# poker_shematics_3.net
KiCad netlist of a schematic drawn in Altium Designer
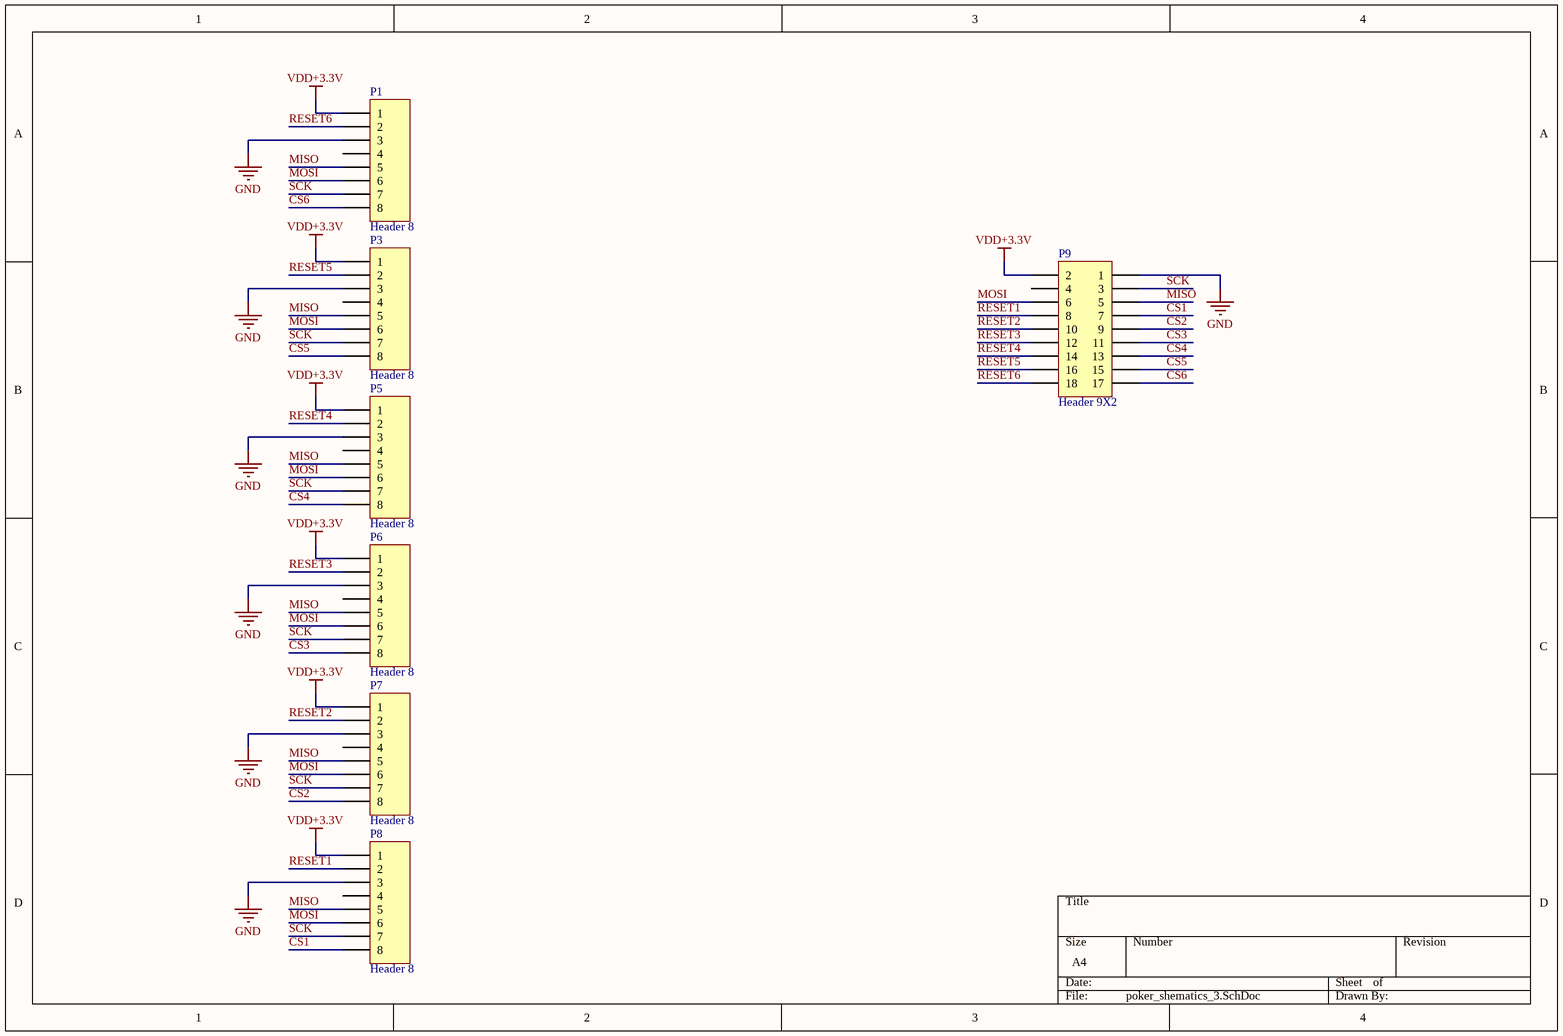
[diagram p0: poker_shematics_3.SchDoc]

(export (version "E")
  (design (tool "Eeschema 10.0.6"))
  (components
    (comp (ref "P1")
      (value "Header 8")
      (footprint "HDR1X8")
      (description "Header, 8-Pin")
      (fields (field (name "PUBLISHER") "Altium Limited"))
      (libsource (lib "Miscellaneous Connectors") (part "Header 8"))
    )
    (comp (ref "P3")
      (value "Header 8")
      (footprint "HDR1X8")
      (description "Header, 8-Pin")
      (fields (field (name "PUBLISHER") "Altium Limited"))
      (libsource (lib "Miscellaneous Connectors") (part "Header 8"))
    )
    (comp (ref "P5")
      (value "Header 8")
      (footprint "HDR1X8")
      (description "Header, 8-Pin")
      (fields (field (name "PUBLISHER") "Altium Limited"))
      (libsource (lib "Miscellaneous Connectors") (part "Header 8"))
    )
    (comp (ref "P6")
      (value "Header 8")
      (footprint "HDR1X8")
      (description "Header, 8-Pin")
      (fields (field (name "PUBLISHER") "Altium Limited"))
      (libsource (lib "Miscellaneous Connectors") (part "Header 8"))
    )
    (comp (ref "P7")
      (value "Header 8")
      (footprint "HDR1X8")
      (description "Header, 8-Pin")
      (fields (field (name "PUBLISHER") "Altium Limited"))
      (libsource (lib "Miscellaneous Connectors") (part "Header 8"))
    )
    (comp (ref "P8")
      (value "Header 8")
      (footprint "HDR1X8")
      (description "Header, 8-Pin")
      (fields (field (name "PUBLISHER") "Altium Limited"))
      (libsource (lib "Miscellaneous Connectors") (part "Header 8"))
    )
    (comp (ref "P9")
      (value "Header 9X2")
      (footprint "HDR2X9")
      (description "Header, 9-Pin, Dual row")
      (fields (field (name "PUBLISHER") "Altium Limited"))
      (libsource (lib "Miscellaneous Connectors") (part "Header 9X2"))
    )
  )
  (nets
    (net (code "1") (name "/CS1") (class "Default")
      (node (ref "P8") (pin "8") (pinfunction "8_8") (pintype "passive"))
      (node (ref "P9") (pin "7") (pinfunction "7_7") (pintype "passive"))
    )
    (net (code "2") (name "/CS2") (class "Default")
      (node (ref "P7") (pin "8") (pinfunction "8_8") (pintype "passive"))
      (node (ref "P9") (pin "9") (pinfunction "9_9") (pintype "passive"))
    )
    (net (code "3") (name "/CS3") (class "Default")
      (node (ref "P6") (pin "8") (pinfunction "8_8") (pintype "passive"))
      (node (ref "P9") (pin "11") (pinfunction "11_11") (pintype "passive"))
    )
    (net (code "4") (name "/CS4") (class "Default")
      (node (ref "P5") (pin "8") (pinfunction "8_8") (pintype "passive"))
      (node (ref "P9") (pin "13") (pinfunction "13_13") (pintype "passive"))
    )
    (net (code "5") (name "/CS5") (class "Default")
      (node (ref "P3") (pin "8") (pinfunction "8_8") (pintype "passive"))
      (node (ref "P9") (pin "15") (pinfunction "15_15") (pintype "passive"))
    )
    (net (code "6") (name "/CS6") (class "Default")
      (node (ref "P1") (pin "8") (pinfunction "8_8") (pintype "passive"))
      (node (ref "P9") (pin "17") (pinfunction "17_17") (pintype "passive"))
    )
    (net (code "7") (name "/MISO") (class "Default")
      (node (ref "P1") (pin "5") (pinfunction "5_5") (pintype "passive"))
      (node (ref "P3") (pin "5") (pinfunction "5_5") (pintype "passive"))
      (node (ref "P5") (pin "5") (pinfunction "5_5") (pintype "passive"))
      (node (ref "P6") (pin "5") (pinfunction "5_5") (pintype "passive"))
      (node (ref "P7") (pin "5") (pinfunction "5_5") (pintype "passive"))
      (node (ref "P8") (pin "5") (pinfunction "5_5") (pintype "passive"))
      (node (ref "P9") (pin "5") (pinfunction "5_5") (pintype "passive"))
    )
    (net (code "8") (name "/MOSI") (class "Default")
      (node (ref "P1") (pin "6") (pinfunction "6_6") (pintype "passive"))
      (node (ref "P3") (pin "6") (pinfunction "6_6") (pintype "passive"))
      (node (ref "P5") (pin "6") (pinfunction "6_6") (pintype "passive"))
      (node (ref "P6") (pin "6") (pinfunction "6_6") (pintype "passive"))
      (node (ref "P7") (pin "6") (pinfunction "6_6") (pintype "passive"))
      (node (ref "P8") (pin "6") (pinfunction "6_6") (pintype "passive"))
      (node (ref "P9") (pin "6") (pinfunction "6_6") (pintype "passive"))
    )
    (net (code "9") (name "/RESET1") (class "Default")
      (node (ref "P8") (pin "2") (pinfunction "2_2") (pintype "passive"))
      (node (ref "P9") (pin "8") (pinfunction "8_8") (pintype "passive"))
    )
    (net (code "10") (name "/RESET2") (class "Default")
      (node (ref "P7") (pin "2") (pinfunction "2_2") (pintype "passive"))
      (node (ref "P9") (pin "10") (pinfunction "10_10") (pintype "passive"))
    )
    (net (code "11") (name "/RESET3") (class "Default")
      (node (ref "P6") (pin "2") (pinfunction "2_2") (pintype "passive"))
      (node (ref "P9") (pin "12") (pinfunction "12_12") (pintype "passive"))
    )
    (net (code "12") (name "/RESET4") (class "Default")
      (node (ref "P5") (pin "2") (pinfunction "2_2") (pintype "passive"))
      (node (ref "P9") (pin "14") (pinfunction "14_14") (pintype "passive"))
    )
    (net (code "13") (name "/RESET5") (class "Default")
      (node (ref "P3") (pin "2") (pinfunction "2_2") (pintype "passive"))
      (node (ref "P9") (pin "16") (pinfunction "16_16") (pintype "passive"))
    )
    (net (code "14") (name "/RESET6") (class "Default")
      (node (ref "P1") (pin "2") (pinfunction "2_2") (pintype "passive"))
      (node (ref "P9") (pin "18") (pinfunction "18_18") (pintype "passive"))
    )
    (net (code "15") (name "/SCK") (class "Default")
      (node (ref "P1") (pin "7") (pinfunction "7_7") (pintype "passive"))
      (node (ref "P3") (pin "7") (pinfunction "7_7") (pintype "passive"))
      (node (ref "P5") (pin "7") (pinfunction "7_7") (pintype "passive"))
      (node (ref "P6") (pin "7") (pinfunction "7_7") (pintype "passive"))
      (node (ref "P7") (pin "7") (pinfunction "7_7") (pintype "passive"))
      (node (ref "P8") (pin "7") (pinfunction "7_7") (pintype "passive"))
      (node (ref "P9") (pin "3") (pinfunction "3_3") (pintype "passive"))
    )
    (net (code "16") (name "GND") (class "Default")
      (node (ref "P1") (pin "3") (pinfunction "3_3") (pintype "passive"))
      (node (ref "P3") (pin "3") (pinfunction "3_3") (pintype "passive"))
      (node (ref "P5") (pin "3") (pinfunction "3_3") (pintype "passive"))
      (node (ref "P6") (pin "3") (pinfunction "3_3") (pintype "passive"))
      (node (ref "P7") (pin "3") (pinfunction "3_3") (pintype "passive"))
      (node (ref "P8") (pin "3") (pinfunction "3_3") (pintype "passive"))
      (node (ref "P9") (pin "1") (pinfunction "1_1") (pintype "passive"))
    )
    (net (code "17") (name "VDD+3.3V") (class "Default")
      (node (ref "P1") (pin "1") (pinfunction "1_1") (pintype "passive"))
      (node (ref "P3") (pin "1") (pinfunction "1_1") (pintype "passive"))
      (node (ref "P5") (pin "1") (pinfunction "1_1") (pintype "passive"))
      (node (ref "P6") (pin "1") (pinfunction "1_1") (pintype "passive"))
      (node (ref "P7") (pin "1") (pinfunction "1_1") (pintype "passive"))
      (node (ref "P8") (pin "1") (pinfunction "1_1") (pintype "passive"))
      (node (ref "P9") (pin "2") (pinfunction "2_2") (pintype "passive"))
    )
    (net (code "18") (name "unconnected-(P1-Pad4)") (class "Default")
      (node (ref "P1") (pin "4") (pinfunction "4_4") (pintype "passive"))
    )
    (net (code "19") (name "unconnected-(P3-Pad4)") (class "Default")
      (node (ref "P3") (pin "4") (pinfunction "4_4") (pintype "passive"))
    )
    (net (code "20") (name "unconnected-(P5-Pad4)") (class "Default")
      (node (ref "P5") (pin "4") (pinfunction "4_4") (pintype "passive"))
    )
    (net (code "21") (name "unconnected-(P6-Pad4)") (class "Default")
      (node (ref "P6") (pin "4") (pinfunction "4_4") (pintype "passive"))
    )
    (net (code "22") (name "unconnected-(P7-Pad4)") (class "Default")
      (node (ref "P7") (pin "4") (pinfunction "4_4") (pintype "passive"))
    )
    (net (code "23") (name "unconnected-(P8-Pad4)") (class "Default")
      (node (ref "P8") (pin "4") (pinfunction "4_4") (pintype "passive"))
    )
    (net (code "24") (name "unconnected-(P9-Pad4)") (class "Default")
      (node (ref "P9") (pin "4") (pinfunction "4_4") (pintype "passive"))
    )
  )
)
